# PERIPHERAL.net
KiCad netlist of a schematic drawn in Altium Designer
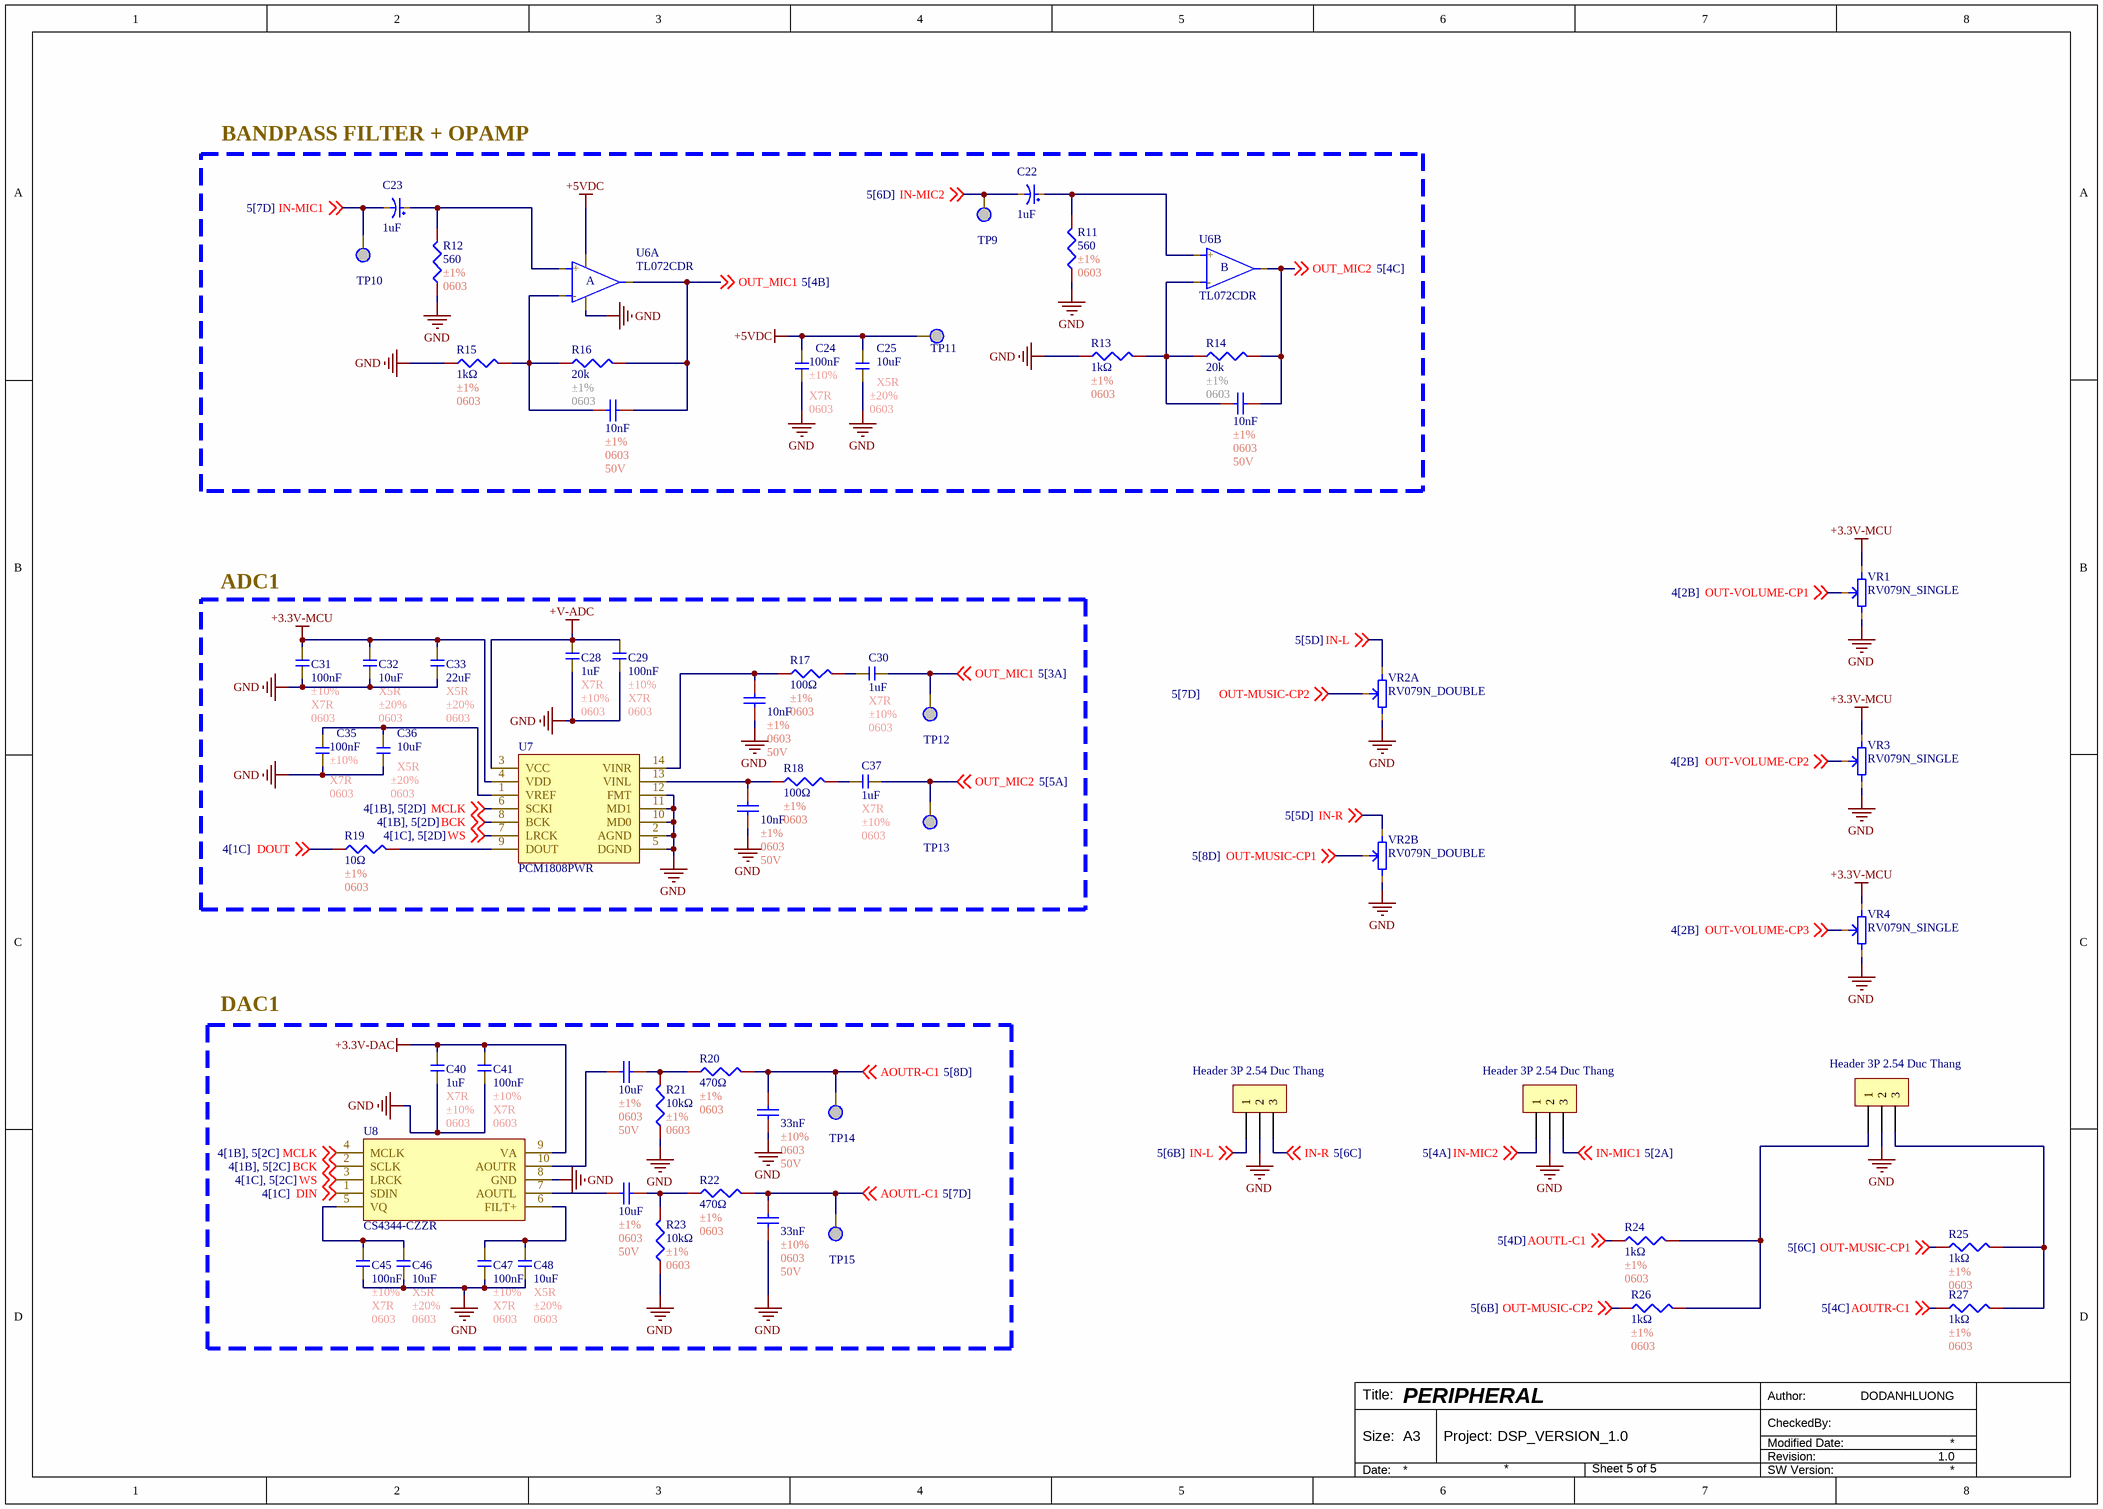
[diagram p0: PERIPHERAL.SchDoc]

(export (version "E")
  (design (tool "Eeschema 10.0.6"))
  (components
    (comp (ref "C22")
      (value "1uF")
      (footprint "C_TH_5x11mm")
      (description "10uF 50V ±20% Through Hole,D5xL11mm Aluminum Electrolytic Capacitors - Leaded ROHS")
      (fields (field (name "MANUFACTURER") "Rubycon") (field (name "MFR. PART #") "50YXF10MEFC5X11"))
      (libsource (lib "Capital") (part "C_10uF_5x11TH"))
    )
    (comp (ref "C23")
      (value "1uF")
      (footprint "C_TH_5x11mm")
      (description "10uF 50V ±20% Through Hole,D5xL11mm Aluminum Electrolytic Capacitors - Leaded ROHS")
      (fields (field (name "MANUFACTURER") "Rubycon") (field (name "MFR. PART #") "50YXF10MEFC5X11"))
      (libsource (lib "Capital") (part "C_10uF_5x11TH"))
    )
    (comp (ref "C24")
      (value "100nF")
      (footprint "C0603")
      (description "50V 100nF X7R ±10% 0603 Multilayer Ceramic Capacitors MLCC - SMD/SMT ROHS")
      (fields
        (field (name "MANUFACTURER") "YAGEO")
        (field (name "MFR. PART #") "CC0603KRX7R9BB104")
        (field (name "TOLERANCE") "±10%")
        (field (name "TEMPERATURE COEFFICIENT") "X7R")
        (field (name "PACKAGE") "0603")
      )
      (libsource (lib "DSP_VERSION_1.0") (part "C0603_100nF_±10%_X7R"))
    )
    (comp (ref "C25")
      (value "10uF")
      (footprint "C0603")
      (description "25V 10uF X5R ±20% 0603 Multilayer Ceramic Capacitors MLCC - SMD/SMT ROHS")
      (fields
        (field (name "MANUFACTURER") "YAGEO")
        (field (name "MFR. PART #") "CC0603MRX5R8BB106")
        (field (name "TEMPERATURE COEFFICIENT") "X5R")
        (field (name "TOLERANCE") "±20%")
        (field (name "PACKAGE") "0603")
      )
      (libsource (lib "DSP_VERSION_1.0") (part "C0603_10uF_±10%_X7R"))
    )
    (comp (ref "C26")
      (value "10nF")
      (footprint "C0603")
      (description "50V 10pF NP0 ±1% 0402 Multilayer Ceramic Capacitors MLCC - SMD/SMT ROHS")
      (fields
        (field (name "MANUFACTURER") "YAGEO")
        (field (name "MFR. PART #") "CC0402FRNPO9BN100")
        (field (name "TOLERANCE") "±1%")
        (field (name "PACKAGE") "0603")
        (field (name "VOLTAGE RATING") "50V")
      )
      (libsource (lib "Capital") (part "C0603_10nF_±1%"))
    )
    (comp (ref "C27")
      (value "10nF")
      (footprint "C0603")
      (description "50V 10pF NP0 ±1% 0402 Multilayer Ceramic Capacitors MLCC - SMD/SMT ROHS")
      (fields
        (field (name "MANUFACTURER") "YAGEO")
        (field (name "MFR. PART #") "CC0402FRNPO9BN100")
        (field (name "TOLERANCE") "±1%")
        (field (name "PACKAGE") "0603")
        (field (name "VOLTAGE RATING") "50V")
      )
      (libsource (lib "Capital") (part "C0603_10nF_±1%"))
    )
    (comp (ref "C28")
      (value "1uF")
      (footprint "C0603")
      (description "50V 1uF X7R ±10% 0603 Multilayer Ceramic Capacitors MLCC - SMD/SMT ROHS")
      (fields
        (field (name "MANUFACTURER") "YAGEO")
        (field (name "MFR. PART #") "CC0603KRX7R9BB105")
        (field (name "TEMPERATURE COEFFICIENT") "X7R")
        (field (name "TOLERANCE") "±10%")
        (field (name "PACKAGE") "0603")
      )
      (libsource (lib "DSP_VERSION_1.0") (part "C0603_1uF_±10%_X7R"))
    )
    (comp (ref "C29")
      (value "100nF")
      (footprint "C0603")
      (description "50V 100nF X7R ±10% 0603 Multilayer Ceramic Capacitors MLCC - SMD/SMT ROHS")
      (fields
        (field (name "MANUFACTURER") "YAGEO")
        (field (name "MFR. PART #") "CC0603KRX7R9BB104")
        (field (name "TOLERANCE") "±10%")
        (field (name "TEMPERATURE COEFFICIENT") "X7R")
        (field (name "PACKAGE") "0603")
      )
      (libsource (lib "DSP_VERSION_1.0") (part "C0603_100nF_±10%_X7R"))
    )
    (comp (ref "C30")
      (value "1uF")
      (footprint "C0603")
      (description "50V 1uF X7R ±10% 0603 Multilayer Ceramic Capacitors MLCC - SMD/SMT ROHS")
      (fields
        (field (name "MANUFACTURER") "YAGEO")
        (field (name "MFR. PART #") "CC0603KRX7R9BB105")
        (field (name "TEMPERATURE COEFFICIENT") "X7R")
        (field (name "TOLERANCE") "±10%")
        (field (name "PACKAGE") "0603")
      )
      (libsource (lib "DSP_VERSION_1.0") (part "C0603_1uF_±10%_X7R"))
    )
    (comp (ref "C31")
      (value "100nF")
      (footprint "C0603")
      (description "50V 100nF X7R ±10% 0603 Multilayer Ceramic Capacitors MLCC - SMD/SMT ROHS")
      (fields
        (field (name "MANUFACTURER") "YAGEO")
        (field (name "MFR. PART #") "CC0603KRX7R9BB104")
        (field (name "TOLERANCE") "±10%")
        (field (name "TEMPERATURE COEFFICIENT") "X7R")
        (field (name "PACKAGE") "0603")
      )
      (libsource (lib "DSP_VERSION_1.0") (part "C0603_100nF_±10%_X7R"))
    )
    (comp (ref "C32")
      (value "10uF")
      (footprint "C0603")
      (description "25V 10uF X5R ±20% 0603 Multilayer Ceramic Capacitors MLCC - SMD/SMT ROHS")
      (fields
        (field (name "MANUFACTURER") "YAGEO")
        (field (name "MFR. PART #") "CC0603MRX5R8BB106")
        (field (name "TEMPERATURE COEFFICIENT") "X5R")
        (field (name "TOLERANCE") "±20%")
        (field (name "PACKAGE") "0603")
      )
      (libsource (lib "DSP_VERSION_1.0") (part "C0603_10uF_±10%_X7R"))
    )
    (comp (ref "C33")
      (value "22uF")
      (footprint "C0603")
      (description "6.3V 22uF X5R ±20% 0603 Multilayer Ceramic Capacitors MLCC - SMD/SMT ROHS")
      (fields
        (field (name "MANUFACTURER") "YAGEO")
        (field (name "MFR. PART #") "CC0603MRX5R5BB226")
        (field (name "TEMPERATURE COEFFICIENT") "X5R")
        (field (name "TOLERANCE") "±20%")
        (field (name "PACKAGE") "0603")
      )
      (libsource (lib "DSP_VERSION_1.0") (part "C0603_22uF_±20%_X5R"))
    )
    (comp (ref "C34")
      (value "10nF")
      (footprint "C0603")
      (description "50V 10pF NP0 ±1% 0402 Multilayer Ceramic Capacitors MLCC - SMD/SMT ROHS")
      (fields
        (field (name "MANUFACTURER") "YAGEO")
        (field (name "MFR. PART #") "CC0402FRNPO9BN100")
        (field (name "TOLERANCE") "±1%")
        (field (name "PACKAGE") "0603")
        (field (name "VOLTAGE RATING") "50V")
      )
      (libsource (lib "Capital") (part "C0603_10nF_±1%"))
    )
    (comp (ref "C35")
      (value "100nF")
      (footprint "C0603")
      (description "50V 100nF X7R ±10% 0603 Multilayer Ceramic Capacitors MLCC - SMD/SMT ROHS")
      (fields
        (field (name "MANUFACTURER") "YAGEO")
        (field (name "MFR. PART #") "CC0603KRX7R9BB104")
        (field (name "TOLERANCE") "±10%")
        (field (name "TEMPERATURE COEFFICIENT") "X7R")
        (field (name "PACKAGE") "0603")
      )
      (libsource (lib "DSP_VERSION_1.0") (part "C0603_100nF_±10%_X7R"))
    )
    (comp (ref "C36")
      (value "10uF")
      (footprint "C0603")
      (description "25V 10uF X5R ±20% 0603 Multilayer Ceramic Capacitors MLCC - SMD/SMT ROHS")
      (fields
        (field (name "MANUFACTURER") "YAGEO")
        (field (name "MFR. PART #") "CC0603MRX5R8BB106")
        (field (name "TEMPERATURE COEFFICIENT") "X5R")
        (field (name "TOLERANCE") "±20%")
        (field (name "PACKAGE") "0603")
      )
      (libsource (lib "DSP_VERSION_1.0") (part "C0603_10uF_±10%_X7R"))
    )
    (comp (ref "C37")
      (value "1uF")
      (footprint "C0603")
      (description "50V 1uF X7R ±10% 0603 Multilayer Ceramic Capacitors MLCC - SMD/SMT ROHS")
      (fields
        (field (name "MANUFACTURER") "YAGEO")
        (field (name "MFR. PART #") "CC0603KRX7R9BB105")
        (field (name "TEMPERATURE COEFFICIENT") "X7R")
        (field (name "TOLERANCE") "±10%")
        (field (name "PACKAGE") "0603")
      )
      (libsource (lib "DSP_VERSION_1.0") (part "C0603_1uF_±10%_X7R"))
    )
    (comp (ref "C38")
      (value "10nF")
      (footprint "C0603")
      (description "50V 10pF NP0 ±1% 0402 Multilayer Ceramic Capacitors MLCC - SMD/SMT ROHS")
      (fields
        (field (name "MANUFACTURER") "YAGEO")
        (field (name "MFR. PART #") "CC0402FRNPO9BN100")
        (field (name "TOLERANCE") "±1%")
        (field (name "PACKAGE") "0603")
        (field (name "VOLTAGE RATING") "50V")
      )
      (libsource (lib "Capital") (part "C0603_10nF_±1%"))
    )
    (comp (ref "C39")
      (value "10uF")
      (footprint "C0603")
      (description "50V 10pF NP0 ±1% 0402 Multilayer Ceramic Capacitors MLCC - SMD/SMT ROHS")
      (fields
        (field (name "MANUFACTURER") "YAGEO")
        (field (name "MFR. PART #") "CC0402FRNPO9BN100")
        (field (name "TOLERANCE") "±1%")
        (field (name "PACKAGE") "0603")
        (field (name "VOLTAGE RATING") "50V")
      )
      (libsource (lib "Capital") (part "C0603_10uF_±1%"))
    )
    (comp (ref "C40")
      (value "1uF")
      (footprint "C0603")
      (description "50V 1uF X7R ±10% 0603 Multilayer Ceramic Capacitors MLCC - SMD/SMT ROHS")
      (fields
        (field (name "MANUFACTURER") "YAGEO")
        (field (name "MFR. PART #") "CC0603KRX7R9BB105")
        (field (name "TEMPERATURE COEFFICIENT") "X7R")
        (field (name "TOLERANCE") "±10%")
        (field (name "PACKAGE") "0603")
      )
      (libsource (lib "DSP_VERSION_1.0") (part "C0603_1uF_±10%_X7R"))
    )
    (comp (ref "C41")
      (value "100nF")
      (footprint "C0603")
      (description "50V 100nF X7R ±10% 0603 Multilayer Ceramic Capacitors MLCC - SMD/SMT ROHS")
      (fields
        (field (name "MANUFACTURER") "YAGEO")
        (field (name "MFR. PART #") "CC0603KRX7R9BB104")
        (field (name "TOLERANCE") "±10%")
        (field (name "TEMPERATURE COEFFICIENT") "X7R")
        (field (name "PACKAGE") "0603")
      )
      (libsource (lib "DSP_VERSION_1.0") (part "C0603_100nF_±10%_X7R"))
    )
    (comp (ref "C42")
      (value "33nF")
      (footprint "C0603")
      (description "100mW Thick Film Resistor 75V ±100ppm/℃ ±1% 470Ω 0603 Chip Resistor - Surface Mount ROHS")
      (fields
        (field (name "MANUFACTURER") "YAGEO")
        (field (name "MFR. PART #") "CC0603KRX7R9BB333")
        (field (name "TOLERANCE") "±10%")
        (field (name "PACKAGE") "0603")
        (field (name "VOLTAGE RATING") "50V")
      )
      (libsource (lib "Capital") (part "C0603_33nF_±10%"))
    )
    (comp (ref "C43")
      (value "10uF")
      (footprint "C0603")
      (description "50V 10pF NP0 ±1% 0402 Multilayer Ceramic Capacitors MLCC - SMD/SMT ROHS")
      (fields
        (field (name "MANUFACTURER") "YAGEO")
        (field (name "MFR. PART #") "CC0402FRNPO9BN100")
        (field (name "TOLERANCE") "±1%")
        (field (name "PACKAGE") "0603")
        (field (name "VOLTAGE RATING") "50V")
      )
      (libsource (lib "Capital") (part "C0603_10uF_±1%"))
    )
    (comp (ref "C44")
      (value "33nF")
      (footprint "C0603")
      (description "100mW Thick Film Resistor 75V ±100ppm/℃ ±1% 470Ω 0603 Chip Resistor - Surface Mount ROHS")
      (fields
        (field (name "MANUFACTURER") "YAGEO")
        (field (name "MFR. PART #") "CC0603KRX7R9BB333")
        (field (name "TOLERANCE") "±10%")
        (field (name "PACKAGE") "0603")
        (field (name "VOLTAGE RATING") "50V")
      )
      (libsource (lib "Capital") (part "C0603_33nF_±10%"))
    )
    (comp (ref "C45")
      (value "100nF")
      (footprint "C0603")
      (description "50V 100nF X7R ±10% 0603 Multilayer Ceramic Capacitors MLCC - SMD/SMT ROHS")
      (fields
        (field (name "MANUFACTURER") "YAGEO")
        (field (name "MFR. PART #") "CC0603KRX7R9BB104")
        (field (name "TOLERANCE") "±10%")
        (field (name "TEMPERATURE COEFFICIENT") "X7R")
        (field (name "PACKAGE") "0603")
      )
      (libsource (lib "DSP_VERSION_1.0") (part "C0603_100nF_±10%_X7R"))
    )
    (comp (ref "C46")
      (value "10uF")
      (footprint "C0603")
      (description "25V 10uF X5R ±20% 0603 Multilayer Ceramic Capacitors MLCC - SMD/SMT ROHS")
      (fields
        (field (name "MANUFACTURER") "YAGEO")
        (field (name "MFR. PART #") "CC0603MRX5R8BB106")
        (field (name "TEMPERATURE COEFFICIENT") "X5R")
        (field (name "TOLERANCE") "±20%")
        (field (name "PACKAGE") "0603")
      )
      (libsource (lib "DSP_VERSION_1.0") (part "C0603_10uF_±10%_X7R"))
    )
    (comp (ref "C47")
      (value "100nF")
      (footprint "C0603")
      (description "50V 100nF X7R ±10% 0603 Multilayer Ceramic Capacitors MLCC - SMD/SMT ROHS")
      (fields
        (field (name "MANUFACTURER") "YAGEO")
        (field (name "MFR. PART #") "CC0603KRX7R9BB104")
        (field (name "TOLERANCE") "±10%")
        (field (name "TEMPERATURE COEFFICIENT") "X7R")
        (field (name "PACKAGE") "0603")
      )
      (libsource (lib "DSP_VERSION_1.0") (part "C0603_100nF_±10%_X7R"))
    )
    (comp (ref "C48")
      (value "10uF")
      (footprint "C0603")
      (description "25V 10uF X5R ±20% 0603 Multilayer Ceramic Capacitors MLCC - SMD/SMT ROHS")
      (fields
        (field (name "MANUFACTURER") "YAGEO")
        (field (name "MFR. PART #") "CC0603MRX5R8BB106")
        (field (name "TEMPERATURE COEFFICIENT") "X5R")
        (field (name "TOLERANCE") "±20%")
        (field (name "PACKAGE") "0603")
      )
      (libsource (lib "DSP_VERSION_1.0") (part "C0603_10uF_±10%_X7R"))
    )
    (comp (ref "H1")
      (value "Header 3P 2.54 Duc Thang")
      (footprint "XH2.54M-3")
      (description "Cắm")
      (libsource (lib "Header") (part "Header 3P 2.54 Duc Thang"))
    )
    (comp (ref "H2")
      (value "Header 3P 2.54 Duc Thang")
      (footprint "XH2.54M-3")
      (description "Cắm")
      (libsource (lib "Header") (part "Header 3P 2.54 Duc Thang"))
    )
    (comp (ref "H3")
      (value "Header 3P 2.54 Duc Thang")
      (footprint "XH2.54M-3")
      (description "Cắm")
      (libsource (lib "Header") (part "Header 3P 2.54 Duc Thang"))
    )
    (comp (ref "R11")
      (value "560")
      (footprint "R0603")
      (description "62.5mW Thick Film Resistor 50V ±1% ±200ppm/℃ 10Ω 0402 Chip Resistor - Surface Mount ROHS")
      (fields
        (field (name "MANUFACTURER") "YAGEO")
        (field (name "MFR. PART #") "RC0402FR-0710RL")
        (field (name "TOLERANCE") "±1%")
        (field (name "PACKAGE") "0603")
      )
      (libsource (lib "Resistor") (part "R0603_10kΩ_±1%"))
    )
    (comp (ref "R12")
      (value "560")
      (footprint "R0603")
      (description "62.5mW Thick Film Resistor 50V ±1% ±200ppm/℃ 10Ω 0402 Chip Resistor - Surface Mount ROHS")
      (fields
        (field (name "MANUFACTURER") "YAGEO")
        (field (name "MFR. PART #") "RC0402FR-0710RL")
        (field (name "TOLERANCE") "±1%")
        (field (name "PACKAGE") "0603")
      )
      (libsource (lib "Resistor") (part "R0603_10kΩ_±1%"))
    )
    (comp (ref "R13")
      (value "1kΩ")
      (footprint "R0603")
      (description "62.5mW Thick Film Resistor 50V ±1% ±200ppm/℃ 10Ω 0402 Chip Resistor - Surface Mount ROHS")
      (fields
        (field (name "MANUFACTURER") "YAGEO")
        (field (name "MFR. PART #") "RC0402FR-0710RL")
        (field (name "TOLERANCE") "±1%")
        (field (name "PACKAGE") "0603")
      )
      (libsource (lib "Resistor") (part "R0603_1kΩ_±1%"))
    )
    (comp (ref "R14")
      (value "20k")
      (footprint "R0603")
      (description "100mW Thick Film Resistor 75V ±100ppm/℃ ±1% 5.1kΩ 0603 Chip Resistor - Surface Mount ROHS")
      (fields
        (field (name "MANUFACTURER") "FOJAN")
        (field (name "MFR. PART #") "FRC0603F5101TS")
        (field (name "TOLERANCE") "±1%")
        (field (name "PACKAGE") "0603")
      )
      (libsource (lib "Resistor") (part "R0603_5k1Ω_±1%"))
    )
    (comp (ref "R15")
      (value "1kΩ")
      (footprint "R0603")
      (description "62.5mW Thick Film Resistor 50V ±1% ±200ppm/℃ 10Ω 0402 Chip Resistor - Surface Mount ROHS")
      (fields
        (field (name "MANUFACTURER") "YAGEO")
        (field (name "MFR. PART #") "RC0402FR-0710RL")
        (field (name "TOLERANCE") "±1%")
        (field (name "PACKAGE") "0603")
      )
      (libsource (lib "Resistor") (part "R0603_1kΩ_±1%"))
    )
    (comp (ref "R16")
      (value "20k")
      (footprint "R0603")
      (description "100mW Thick Film Resistor 75V ±100ppm/℃ ±1% 5.1kΩ 0603 Chip Resistor - Surface Mount ROHS")
      (fields
        (field (name "MANUFACTURER") "FOJAN")
        (field (name "MFR. PART #") "FRC0603F5101TS")
        (field (name "TOLERANCE") "±1%")
        (field (name "PACKAGE") "0603")
      )
      (libsource (lib "Resistor") (part "R0603_5k1Ω_±1%"))
    )
    (comp (ref "R17")
      (value "100Ω")
      (footprint "R0603")
      (description "62.5mW Thick Film Resistor 50V ±1% ±200ppm/℃ 10Ω 0402 Chip Resistor - Surface Mount ROHS")
      (fields
        (field (name "MANUFACTURER") "YAGEO")
        (field (name "MFR. PART #") "RC0402FR-0710RL")
        (field (name "TOLERANCE") "±1%")
        (field (name "PACKAGE") "0603")
      )
      (libsource (lib "Resistor") (part "R0603_100Ω_±1%"))
    )
    (comp (ref "R18")
      (value "100Ω")
      (footprint "R0603")
      (description "62.5mW Thick Film Resistor 50V ±1% ±200ppm/℃ 10Ω 0402 Chip Resistor - Surface Mount ROHS")
      (fields
        (field (name "MANUFACTURER") "YAGEO")
        (field (name "MFR. PART #") "RC0402FR-0710RL")
        (field (name "TOLERANCE") "±1%")
        (field (name "PACKAGE") "0603")
      )
      (libsource (lib "Resistor") (part "R0603_100Ω_±1%"))
    )
    (comp (ref "R19")
      (value "10Ω")
      (footprint "R0603")
      (description "62.5mW Thick Film Resistor 50V ±1% ±200ppm/℃ 10Ω 0402 Chip Resistor - Surface Mount ROHS")
      (fields
        (field (name "MANUFACTURER") "YAGEO")
        (field (name "MFR. PART #") "RC0402FR-0710RL")
        (field (name "TOLERANCE") "±1%")
        (field (name "PACKAGE") "0603")
      )
      (libsource (lib "Resistor") (part "R0603_10Ω_±1%"))
    )
    (comp (ref "R20")
      (value "470Ω")
      (footprint "R0603")
      (description "62.5mW Thick Film Resistor 50V ±1% ±200ppm/℃ 10Ω 0402 Chip Resistor - Surface Mount ROHS")
      (fields
        (field (name "MANUFACTURER") "YAGEO")
        (field (name "MFR. PART #") "RC0603FR-07470RL")
        (field (name "TOLERANCE") "±1%")
        (field (name "PACKAGE") "0603")
      )
      (libsource (lib "Resistor") (part "R0603_470Ω_±1%_1"))
    )
    (comp (ref "R21")
      (value "10kΩ")
      (footprint "R0603")
      (description "62.5mW Thick Film Resistor 50V ±1% ±200ppm/℃ 10Ω 0402 Chip Resistor - Surface Mount ROHS")
      (fields
        (field (name "MANUFACTURER") "YAGEO")
        (field (name "MFR. PART #") "RC0402FR-0710RL")
        (field (name "TOLERANCE") "±1%")
        (field (name "PACKAGE") "0603")
      )
      (libsource (lib "Resistor") (part "R0603_10kΩ_±1%"))
    )
    (comp (ref "R22")
      (value "470Ω")
      (footprint "R0603")
      (description "62.5mW Thick Film Resistor 50V ±1% ±200ppm/℃ 10Ω 0402 Chip Resistor - Surface Mount ROHS")
      (fields
        (field (name "MANUFACTURER") "YAGEO")
        (field (name "MFR. PART #") "RC0603FR-07470RL")
        (field (name "TOLERANCE") "±1%")
        (field (name "PACKAGE") "0603")
      )
      (libsource (lib "Resistor") (part "R0603_470Ω_±1%_1"))
    )
    (comp (ref "R23")
      (value "10kΩ")
      (footprint "R0603")
      (description "62.5mW Thick Film Resistor 50V ±1% ±200ppm/℃ 10Ω 0402 Chip Resistor - Surface Mount ROHS")
      (fields
        (field (name "MANUFACTURER") "YAGEO")
        (field (name "MFR. PART #") "RC0402FR-0710RL")
        (field (name "TOLERANCE") "±1%")
        (field (name "PACKAGE") "0603")
      )
      (libsource (lib "Resistor") (part "R0603_10kΩ_±1%"))
    )
    (comp (ref "R24")
      (value "1kΩ")
      (footprint "R0603")
      (description "62.5mW Thick Film Resistor 50V ±1% ±200ppm/℃ 10Ω 0402 Chip Resistor - Surface Mount ROHS")
      (fields
        (field (name "MANUFACTURER") "YAGEO")
        (field (name "MFR. PART #") "RC0402FR-0710RL")
        (field (name "TOLERANCE") "±1%")
        (field (name "PACKAGE") "0603")
      )
      (libsource (lib "Resistor") (part "R0603_1kΩ_±1%"))
    )
    (comp (ref "R25")
      (value "1kΩ")
      (footprint "R0603")
      (description "62.5mW Thick Film Resistor 50V ±1% ±200ppm/℃ 10Ω 0402 Chip Resistor - Surface Mount ROHS")
      (fields
        (field (name "MANUFACTURER") "YAGEO")
        (field (name "MFR. PART #") "RC0402FR-0710RL")
        (field (name "TOLERANCE") "±1%")
        (field (name "PACKAGE") "0603")
      )
      (libsource (lib "Resistor") (part "R0603_1kΩ_±1%"))
    )
    (comp (ref "R26")
      (value "1kΩ")
      (footprint "R0603")
      (description "62.5mW Thick Film Resistor 50V ±1% ±200ppm/℃ 10Ω 0402 Chip Resistor - Surface Mount ROHS")
      (fields
        (field (name "MANUFACTURER") "YAGEO")
        (field (name "MFR. PART #") "RC0402FR-0710RL")
        (field (name "TOLERANCE") "±1%")
        (field (name "PACKAGE") "0603")
      )
      (libsource (lib "Resistor") (part "R0603_1kΩ_±1%"))
    )
    (comp (ref "R27")
      (value "1kΩ")
      (footprint "R0603")
      (description "62.5mW Thick Film Resistor 50V ±1% ±200ppm/℃ 10Ω 0402 Chip Resistor - Surface Mount ROHS")
      (fields
        (field (name "MANUFACTURER") "YAGEO")
        (field (name "MFR. PART #") "RC0402FR-0710RL")
        (field (name "TOLERANCE") "±1%")
        (field (name "PACKAGE") "0603")
      )
      (libsource (lib "Resistor") (part "R0603_1kΩ_±1%"))
    )
    (comp (ref "TP9") (value "TP") (footprint "TP") (libsource (lib "Other") (part "TP")))
    (comp (ref "TP10") (value "TP") (footprint "TP") (libsource (lib "Other") (part "TP")))
    (comp (ref "TP11") (value "TP") (footprint "TP") (libsource (lib "Other") (part "TP")))
    (comp (ref "TP12") (value "TP") (footprint "TP") (libsource (lib "Other") (part "TP")))
    (comp (ref "TP13") (value "TP") (footprint "TP") (libsource (lib "Other") (part "TP")))
    (comp (ref "TP14") (value "TP") (footprint "TP") (libsource (lib "Other") (part "TP")))
    (comp (ref "TP15") (value "TP") (footprint "TP") (libsource (lib "Other") (part "TP")))
    (comp (ref "U6")
      (value "TL072CDR")
      (footprint "TL072CDR")
      (description "3mV 65pA 3MHz 13V/us 2 SOIC-8 FET Input Amplifiers ROHS")
      (fields (field (name "MANUFACTURER") "TI") (field (name "LCSC PART #") "C67473"))
      (libsource (lib "IC") (part "TL072CDR"))
    )
    (comp (ref "U7")
      (value "PCM1808PWR")
      (footprint "PCM1808PWR")
      (description "4.5V~5.5V 24 I2S TSSOP-14 ADCs/DACs - Special Purpose ROHS")
      (fields (field (name "MANUFACTURER") "TI") (field (name "LCSC PART #") "C55513"))
      (libsource (lib "IC") (part "PCM1808PWR"))
    )
    (comp (ref "U8")
      (value "CS4344-CZZR")
      (footprint "CS4344-CZZR")
      (description "250ms I2S 3.3V~5V 24 TSSOP-10-3mm Digital to Analog Converters (DAC) ROHS")
      (fields (field (name "MANUFACTURER") "Cirrus Logic") (field (name "LCSC PART #") "C8952"))
      (libsource (lib "IC") (part "CS4344-CZZR"))
    )
    (comp (ref "VR1")
      (value "RV079N_SINGLE")
      (footprint "RK079N_SINGLE")
      (libsource (lib "Resistor") (part "RV079N_SINGLE"))
    )
    (comp (ref "VR2")
      (value "RV079N_DOUBLE")
      (footprint "RK079N_DOUBLE")
      (libsource (lib "Resistor") (part "RV079N_DOUBLE"))
    )
    (comp (ref "VR3")
      (value "RV079N_SINGLE")
      (footprint "RK079N_SINGLE")
      (libsource (lib "Resistor") (part "RV079N_SINGLE"))
    )
    (comp (ref "VR4")
      (value "RV079N_SINGLE")
      (footprint "RK079N_SINGLE")
      (libsource (lib "Resistor") (part "RV079N_SINGLE"))
    )
  )
  (nets
    (net (code "1") (name "+3.3V-DAC") (class "Default")
      (node (ref "C40") (pin "2") (pinfunction "2_2") (pintype "passive"))
      (node (ref "C41") (pin "2") (pinfunction "2_2") (pintype "passive"))
      (node (ref "U8") (pin "9") (pinfunction "VA_9") (pintype "passive"))
    )
    (net (code "2") (name "+3.3V-MCU") (class "Default")
      (node (ref "C31") (pin "2") (pinfunction "2_2") (pintype "passive"))
      (node (ref "C32") (pin "2") (pinfunction "2_2") (pintype "passive"))
      (node (ref "C33") (pin "2") (pinfunction "2_2") (pintype "passive"))
      (node (ref "U7") (pin "4") (pinfunction "VDD_4") (pintype "passive"))
      (node (ref "VR1") (pin "3") (pinfunction "3_3") (pintype "passive"))
      (node (ref "VR3") (pin "3") (pinfunction "3_3") (pintype "passive"))
      (node (ref "VR4") (pin "3") (pinfunction "3_3") (pintype "passive"))
    )
    (net (code "3") (name "+5VDC") (class "Default")
      (node (ref "C24") (pin "2") (pinfunction "2_2") (pintype "passive"))
      (node (ref "C25") (pin "2") (pinfunction "2_2") (pintype "passive"))
      (node (ref "TP11") (pin "1") (pinfunction "1_1") (pintype "passive"))
      (node (ref "U6") (pin "8") (pinfunction "8_8") (pintype "passive"))
    )
    (net (code "4") (name "+V-ADC") (class "Default")
      (node (ref "C28") (pin "2") (pinfunction "2_2") (pintype "passive"))
      (node (ref "C29") (pin "2") (pinfunction "2_2") (pintype "passive"))
      (node (ref "U7") (pin "3") (pinfunction "VCC_3") (pintype "passive"))
    )
    (net (code "5") (name "AOUTL-C1") (class "Default")
      (node (ref "C44") (pin "1") (pinfunction "1_1") (pintype "passive"))
      (node (ref "R22") (pin "2") (pinfunction "2_2") (pintype "passive"))
      (node (ref "R24") (pin "1") (pinfunction "1_1") (pintype "passive"))
      (node (ref "TP15") (pin "1") (pinfunction "1_1") (pintype "passive"))
    )
    (net (code "6") (name "AOUTR-C1") (class "Default")
      (node (ref "C42") (pin "1") (pinfunction "1_1") (pintype "passive"))
      (node (ref "R20") (pin "2") (pinfunction "2_2") (pintype "passive"))
      (node (ref "R27") (pin "1") (pinfunction "1_1") (pintype "passive"))
      (node (ref "TP14") (pin "1") (pinfunction "1_1") (pintype "passive"))
    )
    (net (code "7") (name "BCK") (class "Default")
      (node (ref "U7") (pin "8") (pinfunction "BCK_8") (pintype "passive"))
      (node (ref "U8") (pin "2") (pinfunction "SCLK_2") (pintype "passive"))
    )
    (net (code "8") (name "DIN") (class "Default")
      (node (ref "U8") (pin "1") (pinfunction "SDIN_1") (pintype "passive"))
    )
    (net (code "9") (name "DOUT") (class "Default")
      (node (ref "R19") (pin "1") (pinfunction "1_1") (pintype "passive"))
    )
    (net (code "10") (name "GND") (class "Default")
      (node (ref "C24") (pin "1") (pinfunction "1_1") (pintype "passive"))
      (node (ref "C25") (pin "1") (pinfunction "1_1") (pintype "passive"))
      (node (ref "C28") (pin "1") (pinfunction "1_1") (pintype "passive"))
      (node (ref "C29") (pin "1") (pinfunction "1_1") (pintype "passive"))
      (node (ref "C31") (pin "1") (pinfunction "1_1") (pintype "passive"))
      (node (ref "C32") (pin "1") (pinfunction "1_1") (pintype "passive"))
      (node (ref "C33") (pin "1") (pinfunction "1_1") (pintype "passive"))
      (node (ref "C34") (pin "2") (pinfunction "2_2") (pintype "passive"))
      (node (ref "C35") (pin "1") (pinfunction "1_1") (pintype "passive"))
      (node (ref "C36") (pin "1") (pinfunction "1_1") (pintype "passive"))
      (node (ref "C38") (pin "2") (pinfunction "2_2") (pintype "passive"))
      (node (ref "C40") (pin "1") (pinfunction "1_1") (pintype "passive"))
      (node (ref "C41") (pin "1") (pinfunction "1_1") (pintype "passive"))
      (node (ref "C42") (pin "2") (pinfunction "2_2") (pintype "passive"))
      (node (ref "C44") (pin "2") (pinfunction "2_2") (pintype "passive"))
      (node (ref "C45") (pin "1") (pinfunction "1_1") (pintype "passive"))
      (node (ref "C46") (pin "1") (pinfunction "1_1") (pintype "passive"))
      (node (ref "C47") (pin "1") (pinfunction "1_1") (pintype "passive"))
      (node (ref "C48") (pin "1") (pinfunction "1_1") (pintype "passive"))
      (node (ref "H1") (pin "2") (pinfunction "2_2") (pintype "passive"))
      (node (ref "H2") (pin "2") (pinfunction "2_2") (pintype "passive"))
      (node (ref "H3") (pin "2") (pinfunction "2_2") (pintype "passive"))
      (node (ref "R11") (pin "1") (pinfunction "1_1") (pintype "passive"))
      (node (ref "R12") (pin "1") (pinfunction "1_1") (pintype "passive"))
      (node (ref "R13") (pin "1") (pinfunction "1_1") (pintype "passive"))
      (node (ref "R15") (pin "1") (pinfunction "1_1") (pintype "passive"))
      (node (ref "R21") (pin "1") (pinfunction "1_1") (pintype "passive"))
      (node (ref "R23") (pin "1") (pinfunction "1_1") (pintype "passive"))
      (node (ref "U6") (pin "4") (pinfunction "GND_4") (pintype "passive"))
      (node (ref "U7") (pin "10") (pinfunction "MD0_10") (pintype "passive"))
      (node (ref "U7") (pin "11") (pinfunction "MD1_11") (pintype "passive"))
      (node (ref "U7") (pin "12") (pinfunction "FMT_12") (pintype "passive"))
      (node (ref "U7") (pin "2") (pinfunction "AGND_2") (pintype "passive"))
      (node (ref "U7") (pin "5") (pinfunction "DGND_5") (pintype "passive"))
      (node (ref "U8") (pin "8") (pinfunction "GND_8") (pintype "passive"))
      (node (ref "VR1") (pin "1") (pinfunction "1_1") (pintype "passive"))
      (node (ref "VR2") (pin "1") (pinfunction "1_1") (pintype "passive"))
      (node (ref "VR2") (pin "4") (pinfunction "4_4") (pintype "passive"))
      (node (ref "VR3") (pin "1") (pinfunction "1_1") (pintype "passive"))
      (node (ref "VR4") (pin "1") (pinfunction "1_1") (pintype "passive"))
    )
    (net (code "11") (name "IN-L") (class "Default")
      (node (ref "H2") (pin "1") (pinfunction "1_1") (pintype "passive"))
      (node (ref "VR2") (pin "3") (pinfunction "3_3") (pintype "passive"))
    )
    (net (code "12") (name "IN-MIC1") (class "Default")
      (node (ref "C23") (pin "2") (pinfunction "2_2") (pintype "passive"))
      (node (ref "H3") (pin "3") (pinfunction "3_3") (pintype "passive"))
      (node (ref "TP10") (pin "1") (pinfunction "1_1") (pintype "passive"))
    )
    (net (code "13") (name "IN-MIC2") (class "Default")
      (node (ref "C22") (pin "2") (pinfunction "2_2") (pintype "passive"))
      (node (ref "H3") (pin "1") (pinfunction "1_1") (pintype "passive"))
      (node (ref "TP9") (pin "1") (pinfunction "1_1") (pintype "passive"))
    )
    (net (code "14") (name "IN-R") (class "Default")
      (node (ref "H2") (pin "3") (pinfunction "3_3") (pintype "passive"))
      (node (ref "VR2") (pin "6") (pinfunction "6_6") (pintype "passive"))
    )
    (net (code "15") (name "MCLK") (class "Default")
      (node (ref "U7") (pin "6") (pinfunction "SCKI_6") (pintype "passive"))
      (node (ref "U8") (pin "4") (pinfunction "MCLK_4") (pintype "passive"))
    )
    (net (code "16") (name "Net-(C30-Pad2)") (class "Default")
      (node (ref "C30") (pin "2") (pinfunction "2_2") (pintype "passive"))
      (node (ref "R17") (pin "2") (pinfunction "2_2") (pintype "passive"))
    )
    (net (code "17") (name "Net-(C37-Pad2)") (class "Default")
      (node (ref "C37") (pin "2") (pinfunction "2_2") (pintype "passive"))
      (node (ref "R18") (pin "2") (pinfunction "2_2") (pintype "passive"))
    )
    (net (code "18") (name "Net-(C39-Pad1)") (class "Default")
      (node (ref "C39") (pin "1") (pinfunction "1_1") (pintype "passive"))
      (node (ref "R20") (pin "1") (pinfunction "1_1") (pintype "passive"))
      (node (ref "R21") (pin "2") (pinfunction "2_2") (pintype "passive"))
    )
    (net (code "19") (name "Net-(C43-Pad1)") (class "Default")
      (node (ref "C43") (pin "1") (pinfunction "1_1") (pintype "passive"))
      (node (ref "R22") (pin "1") (pinfunction "1_1") (pintype "passive"))
      (node (ref "R23") (pin "2") (pinfunction "2_2") (pintype "passive"))
    )
    (net (code "20") (name "Net-(H1-Pad1)") (class "Default")
      (node (ref "H1") (pin "1") (pinfunction "1_1") (pintype "passive"))
      (node (ref "R24") (pin "2") (pinfunction "2_2") (pintype "passive"))
      (node (ref "R26") (pin "2") (pinfunction "2_2") (pintype "passive"))
    )
    (net (code "21") (name "Net-(H1-Pad3)") (class "Default")
      (node (ref "H1") (pin "3") (pinfunction "3_3") (pintype "passive"))
      (node (ref "R25") (pin "2") (pinfunction "2_2") (pintype "passive"))
      (node (ref "R27") (pin "2") (pinfunction "2_2") (pintype "passive"))
    )
    (net (code "22") (name "Net-(U6A-+)") (class "Default")
      (node (ref "C23") (pin "1") (pinfunction "1_1") (pintype "passive"))
      (node (ref "R12") (pin "2") (pinfunction "2_2") (pintype "passive"))
      (node (ref "U6") (pin "3") (pinfunction "+_3") (pintype "passive"))
    )
    (net (code "23") (name "Net-(U6A--)") (class "Default")
      (node (ref "C27") (pin "1") (pinfunction "1_1") (pintype "passive"))
      (node (ref "R15") (pin "2") (pinfunction "2_2") (pintype "passive"))
      (node (ref "R16") (pin "1") (pinfunction "1_1") (pintype "passive"))
      (node (ref "U6") (pin "2") (pinfunction "-_2") (pintype "passive"))
    )
    (net (code "24") (name "Net-(U6B-+)") (class "Default")
      (node (ref "C22") (pin "1") (pinfunction "1_1") (pintype "passive"))
      (node (ref "R11") (pin "2") (pinfunction "2_2") (pintype "passive"))
      (node (ref "U6") (pin "5") (pinfunction "+_5") (pintype "passive"))
    )
    (net (code "25") (name "Net-(U6B--)") (class "Default")
      (node (ref "C26") (pin "1") (pinfunction "1_1") (pintype "passive"))
      (node (ref "R13") (pin "2") (pinfunction "2_2") (pintype "passive"))
      (node (ref "R14") (pin "1") (pinfunction "1_1") (pintype "passive"))
      (node (ref "U6") (pin "6") (pinfunction "-_6") (pintype "passive"))
    )
    (net (code "26") (name "Net-(U7-DOUT)") (class "Default")
      (node (ref "R19") (pin "2") (pinfunction "2_2") (pintype "passive"))
      (node (ref "U7") (pin "9") (pinfunction "DOUT_9") (pintype "passive"))
    )
    (net (code "27") (name "Net-(U7-VINL)") (class "Default")
      (node (ref "C38") (pin "1") (pinfunction "1_1") (pintype "passive"))
      (node (ref "R18") (pin "1") (pinfunction "1_1") (pintype "passive"))
      (node (ref "U7") (pin "13") (pinfunction "VINL_13") (pintype "passive"))
    )
    (net (code "28") (name "Net-(U7-VINR)") (class "Default")
      (node (ref "C34") (pin "1") (pinfunction "1_1") (pintype "passive"))
      (node (ref "R17") (pin "1") (pinfunction "1_1") (pintype "passive"))
      (node (ref "U7") (pin "14") (pinfunction "VINR_14") (pintype "passive"))
    )
    (net (code "29") (name "Net-(U7-VREF)") (class "Default")
      (node (ref "C35") (pin "2") (pinfunction "2_2") (pintype "passive"))
      (node (ref "C36") (pin "2") (pinfunction "2_2") (pintype "passive"))
      (node (ref "U7") (pin "1") (pinfunction "VREF_1") (pintype "passive"))
    )
    (net (code "30") (name "Net-(U8-AOUTL)") (class "Default")
      (node (ref "C43") (pin "2") (pinfunction "2_2") (pintype "passive"))
      (node (ref "U8") (pin "7") (pinfunction "AOUTL_7") (pintype "passive"))
    )
    (net (code "31") (name "Net-(U8-AOUTR)") (class "Default")
      (node (ref "C39") (pin "2") (pinfunction "2_2") (pintype "passive"))
      (node (ref "U8") (pin "10") (pinfunction "AOUTR_10") (pintype "passive"))
    )
    (net (code "32") (name "Net-(U8-FILT+)") (class "Default")
      (node (ref "C47") (pin "2") (pinfunction "2_2") (pintype "passive"))
      (node (ref "C48") (pin "2") (pinfunction "2_2") (pintype "passive"))
      (node (ref "U8") (pin "6") (pinfunction "FILT+_6") (pintype "passive"))
    )
    (net (code "33") (name "Net-(U8-VQ)") (class "Default")
      (node (ref "C45") (pin "2") (pinfunction "2_2") (pintype "passive"))
      (node (ref "C46") (pin "2") (pinfunction "2_2") (pintype "passive"))
      (node (ref "U8") (pin "5") (pinfunction "VQ_5") (pintype "passive"))
    )
    (net (code "34") (name "OUT-MUSIC-CP1") (class "Default")
      (node (ref "R25") (pin "1") (pinfunction "1_1") (pintype "passive"))
      (node (ref "VR2") (pin "5") (pinfunction "5_5") (pintype "passive"))
    )
    (net (code "35") (name "OUT-MUSIC-CP2") (class "Default")
      (node (ref "R26") (pin "1") (pinfunction "1_1") (pintype "passive"))
      (node (ref "VR2") (pin "2") (pinfunction "2_2") (pintype "passive"))
    )
    (net (code "36") (name "OUT-VOLUME-CP1") (class "Default")
      (node (ref "VR1") (pin "2") (pinfunction "2_2") (pintype "passive"))
    )
    (net (code "37") (name "OUT-VOLUME-CP2") (class "Default")
      (node (ref "VR3") (pin "2") (pinfunction "2_2") (pintype "passive"))
    )
    (net (code "38") (name "OUT-VOLUME-CP3") (class "Default")
      (node (ref "VR4") (pin "2") (pinfunction "2_2") (pintype "passive"))
    )
    (net (code "39") (name "OUT_MIC1") (class "Default")
      (node (ref "C27") (pin "2") (pinfunction "2_2") (pintype "passive"))
      (node (ref "C30") (pin "1") (pinfunction "1_1") (pintype "passive"))
      (node (ref "R16") (pin "2") (pinfunction "2_2") (pintype "passive"))
      (node (ref "TP12") (pin "1") (pinfunction "1_1") (pintype "passive"))
      (node (ref "U6") (pin "1") (pinfunction "out_1") (pintype "passive"))
    )
    (net (code "40") (name "OUT_MIC2") (class "Default")
      (node (ref "C26") (pin "2") (pinfunction "2_2") (pintype "passive"))
      (node (ref "C37") (pin "1") (pinfunction "1_1") (pintype "passive"))
      (node (ref "R14") (pin "2") (pinfunction "2_2") (pintype "passive"))
      (node (ref "TP13") (pin "1") (pinfunction "1_1") (pintype "passive"))
      (node (ref "U6") (pin "7") (pinfunction "out_7") (pintype "passive"))
    )
    (net (code "41") (name "WS") (class "Default")
      (node (ref "U7") (pin "7") (pinfunction "LRCK_7") (pintype "passive"))
      (node (ref "U8") (pin "3") (pinfunction "LRCK_3") (pintype "passive"))
    )
  )
)
